# Sheet11.net
KiCad netlist of a schematic drawn in Altium Designer
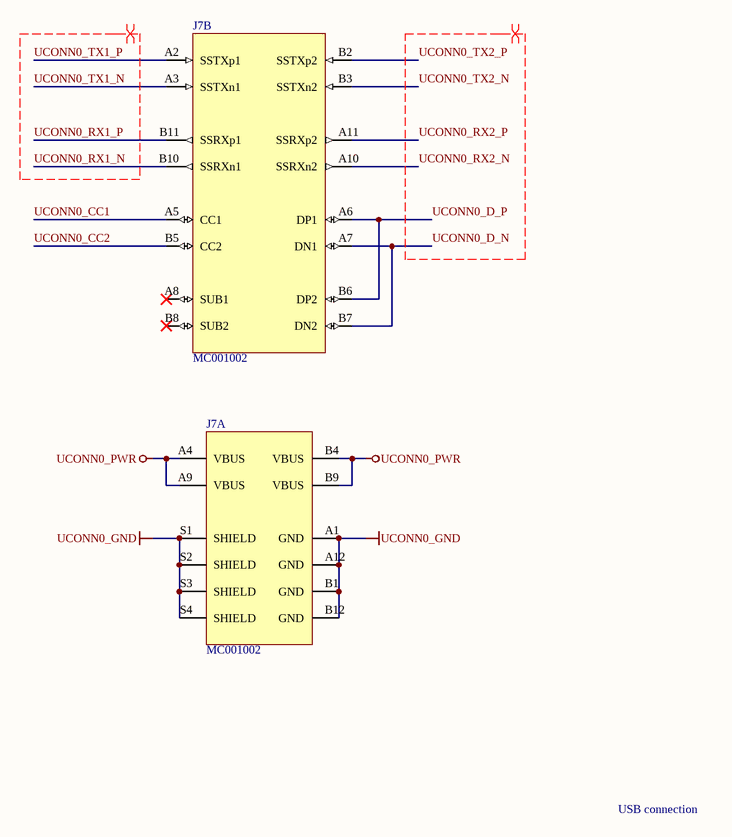
[diagram p0: Sheet11.SchDoc]

(export (version "E")
  (design (tool "Eeschema 10.0.6"))
  (components
    (comp (ref "J7")
      (value "MC001002")
      (footprint "MC001002")
      (description "USB C Female SMT Connector")
      (libsource (lib "Integrated_Library") (part "MC001002"))
    )
  )
  (nets
    (net (code "1") (name "/UCONN0_CC1") (class "Default")
      (node (ref "J7") (pin "A5") (pinfunction "CC1_A5") (pintype "bidirectional"))
    )
    (net (code "2") (name "/UCONN0_CC2") (class "Default")
      (node (ref "J7") (pin "B5") (pinfunction "CC2_B5") (pintype "bidirectional"))
    )
    (net (code "3") (name "/UCONN0_D_N") (class "Default")
      (node (ref "J7") (pin "A7") (pinfunction "DN1_A7") (pintype "bidirectional"))
      (node (ref "J7") (pin "B7") (pinfunction "DN2_B7") (pintype "bidirectional"))
    )
    (net (code "4") (name "/UCONN0_D_P") (class "Default")
      (node (ref "J7") (pin "A6") (pinfunction "DP1_A6") (pintype "bidirectional"))
      (node (ref "J7") (pin "B6") (pinfunction "DP2_B6") (pintype "bidirectional"))
    )
    (net (code "5") (name "/UCONN0_RX1_N") (class "Default")
      (node (ref "J7") (pin "B10") (pinfunction "SSRXn1_B10") (pintype "output"))
    )
    (net (code "6") (name "/UCONN0_RX1_P") (class "Default")
      (node (ref "J7") (pin "B11") (pinfunction "SSRXp1_B11") (pintype "output"))
    )
    (net (code "7") (name "/UCONN0_RX2_N") (class "Default")
      (node (ref "J7") (pin "A10") (pinfunction "SSRXn2_A10") (pintype "output"))
    )
    (net (code "8") (name "/UCONN0_RX2_P") (class "Default")
      (node (ref "J7") (pin "A11") (pinfunction "SSRXp2_A11") (pintype "output"))
    )
    (net (code "9") (name "/UCONN0_TX1_N") (class "Default")
      (node (ref "J7") (pin "A3") (pinfunction "SSTXn1_A3") (pintype "input"))
    )
    (net (code "10") (name "/UCONN0_TX1_P") (class "Default")
      (node (ref "J7") (pin "A2") (pinfunction "SSTXp1_A2") (pintype "input"))
    )
    (net (code "11") (name "/UCONN0_TX2_N") (class "Default")
      (node (ref "J7") (pin "B3") (pinfunction "SSTXn2_B3") (pintype "input"))
    )
    (net (code "12") (name "/UCONN0_TX2_P") (class "Default")
      (node (ref "J7") (pin "B2") (pinfunction "SSTXp2_B2") (pintype "input"))
    )
    (net (code "13") (name "UCONN0_GND") (class "Default")
      (node (ref "J7") (pin "A1") (pinfunction "GND_A1") (pintype "power_in"))
      (node (ref "J7") (pin "A12") (pinfunction "GND_A12") (pintype "power_in"))
      (node (ref "J7") (pin "B1") (pinfunction "GND_B1") (pintype "power_in"))
      (node (ref "J7") (pin "B12") (pinfunction "GND_B12") (pintype "power_in"))
      (node (ref "J7") (pin "S1") (pinfunction "SHIELD_S1") (pintype "power_in"))
      (node (ref "J7") (pin "S2") (pinfunction "SHIELD_S2") (pintype "power_in"))
      (node (ref "J7") (pin "S3") (pinfunction "SHIELD_S3") (pintype "power_in"))
      (node (ref "J7") (pin "S4") (pinfunction "SHIELD_S4") (pintype "power_in"))
    )
    (net (code "14") (name "UCONN0_PWR") (class "Default")
      (node (ref "J7") (pin "A4") (pinfunction "VBUS_A4") (pintype "power_in"))
      (node (ref "J7") (pin "A9") (pinfunction "VBUS_A9") (pintype "power_in"))
      (node (ref "J7") (pin "B4") (pinfunction "VBUS_B4") (pintype "power_in"))
      (node (ref "J7") (pin "B9") (pinfunction "VBUS_B9") (pintype "power_in"))
    )
    (net (code "15") (name "unconnected-(J7B-SUB1-PadA8)") (class "Default")
      (node (ref "J7") (pin "A8") (pinfunction "SUB1_A8") (pintype "bidirectional+no_connect"))
    )
    (net (code "16") (name "unconnected-(J7B-SUB2-PadB8)") (class "Default")
      (node (ref "J7") (pin "B8") (pinfunction "SUB2_B8") (pintype "bidirectional+no_connect"))
    )
  )
)
